# 4_Digital_Isolator.net
KiCad netlist of a schematic drawn in Altium Designer
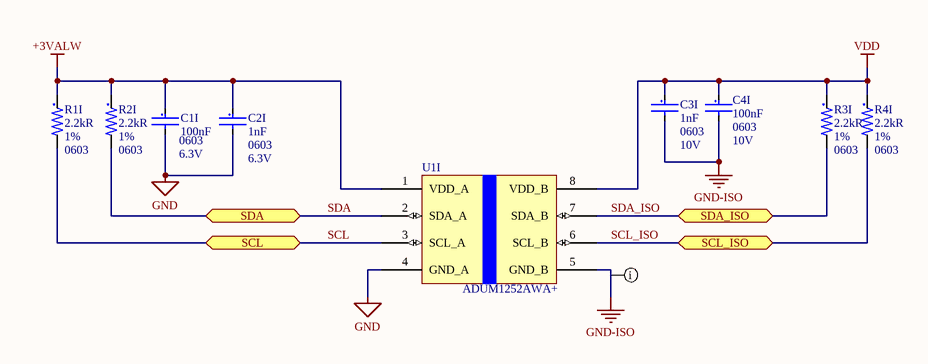
[diagram p0: 4_Digital_Isolator.SchDoc]

(export (version "E")
  (design (tool "Eeschema 10.0.6"))
  (components
    (comp (ref "C1I")
      (value "100nF")
      (footprint "C0603-IPC_C_No_Silk")
      (description "Cap Cer 0.1UF 6.3V X7R 0603")
      (fields
        (field (name "MANUFACTURER") "KYOCERA AVX")
        (field (name "MANUFACTURER PART NUMBER") "KGM15AR70J104KM")
        (field (name "VOLTAGE") "6.3V")
        (field (name "PACKAGE") "0603")
      )
      (libsource (lib "Lib_Capacitor_0603") (part "100nF_6.3V"))
    )
    (comp (ref "C2I")
      (value "1nF")
      (footprint "C0603-IPC_C_No_Silk")
      (description "Cap Ceramic 0.001uF 6.3V C0G 10% SMD 0603 125°C Paper T/R")
      (fields
        (field (name "MANUFACTURER") "Kyocera AVX")
        (field (name "MANUFACTURER PART NUMBER") "06036A102KAT2A")
        (field (name "CASE CODE (IMPERIAL)") "0603")
        (field (name "VOLTAGE RATING") "6.3V")
      )
      (libsource (lib "Lib_Capacitor_0603") (part "1nF_6.3V"))
    )
    (comp (ref "C3I")
      (value "1nF")
      (footprint "C0603-IPC_C_No_Silk")
      (description "Cap Ceramic 0.001uF 10V X7R 10% SMD 0603 125°C Paper T/R")
      (fields
        (field (name "MANUFACTURER") "Yageo")
        (field (name "MANUFACTURER PART NUMBER") "CC0603KRX7R6BB102")
        (field (name "CASE CODE (IMPERIAL)") "0603")
        (field (name "VOLTAGE RATING") "10V")
      )
      (libsource (lib "Lib_Capacitor_0603") (part "1nF_10V"))
    )
    (comp (ref "C4I")
      (value "100nF")
      (footprint "C0603-IPC_C_No_Silk")
      (description "Multilayer Ceramic Capacitor, 0.1 uF, 10 V, ± 10%, X7R, 0603 [1608 Metric]")
      (fields
        (field (name "MANUFACTURER") "KEMET")
        (field (name "MANUFACTURER PART NUMBER") "C0603C104K8RACTU")
        (field (name "VOLTAGE") "10V")
        (field (name "CASE/PACKAGE") "0603")
      )
      (libsource (lib "Lib_Capacitor_0603") (part "100nF_10V"))
    )
    (comp (ref "R1I")
      (value "2.2kR")
      (footprint "R0603-MFG")
      (description "SMD Chip Resistor, 2.2 kOhm, ± 1%, 100 mW, 0603 [1608 Metric], Thick Film, General Purpose")
      (fields
        (field (name "MANUFACTURER") "Yageo")
        (field (name "MANUFACTURER PART NUMBER") "RC0603FR-072K2L")
        (field (name "TOLERANCE") "1%")
        (field (name "CASE/PACKAGE") "0603")
      )
      (libsource (lib "Lib_Register_0603") (part "2.2K"))
    )
    (comp (ref "R2I")
      (value "2.2kR")
      (footprint "R0603-MFG")
      (description "SMD Chip Resistor, 2.2 kOhm, ± 1%, 100 mW, 0603 [1608 Metric], Thick Film, General Purpose")
      (fields
        (field (name "MANUFACTURER") "Yageo")
        (field (name "MANUFACTURER PART NUMBER") "RC0603FR-072K2L")
        (field (name "TOLERANCE") "1%")
        (field (name "CASE/PACKAGE") "0603")
      )
      (libsource (lib "Lib_Register_0603") (part "2.2K"))
    )
    (comp (ref "R3I")
      (value "2.2kR")
      (footprint "R0603-MFG")
      (description "SMD Chip Resistor, 2.2 kOhm, ± 1%, 100 mW, 0603 [1608 Metric], Thick Film, General Purpose")
      (fields
        (field (name "MANUFACTURER") "Yageo")
        (field (name "MANUFACTURER PART NUMBER") "RC0603FR-072K2L")
        (field (name "TOLERANCE") "1%")
        (field (name "CASE/PACKAGE") "0603")
      )
      (libsource (lib "Lib_Register_0603") (part "2.2K"))
    )
    (comp (ref "R4I")
      (value "2.2kR")
      (footprint "R0603-MFG")
      (description "SMD Chip Resistor, 2.2 kOhm, ± 1%, 100 mW, 0603 [1608 Metric], Thick Film, General Purpose")
      (fields
        (field (name "MANUFACTURER") "Yageo")
        (field (name "MANUFACTURER PART NUMBER") "RC0603FR-072K2L")
        (field (name "TOLERANCE") "1%")
        (field (name "CASE/PACKAGE") "0603")
      )
      (libsource (lib "Lib_Register_0603") (part "2.2K"))
    )
    (comp (ref "U1I")
      (value "ADUM1252AWA+")
      (footprint "SOIC-W-8-IPC_A")
      (description "Ultra-Low Power, Bidirectional I2C Isolator with Extended VDD, Idle-Bus Hot-Swap and Low VOL")
      (fields (field (name "MANUFACTURER") "Analog Devices"))
      (libsource (lib "Lib_IC_Voltage_Level_Shift") (part "ADUM1252AWA+"))
    )
  )
  (nets
    (net (code "1") (name "+3VALW") (class "Default")
      (node (ref "C1I") (pin "1") (pinfunction "1_1") (pintype "passive"))
      (node (ref "C2I") (pin "1") (pinfunction "1_1") (pintype "passive"))
      (node (ref "R1I") (pin "1") (pinfunction "1_1") (pintype "passive"))
      (node (ref "R2I") (pin "1") (pinfunction "1_1") (pintype "passive"))
      (node (ref "U1I") (pin "1") (pinfunction "VDD_A_1") (pintype "power_in"))
    )
    (net (code "2") (name "/SCL") (class "Default")
      (node (ref "R1I") (pin "2") (pinfunction "2_2") (pintype "passive"))
      (node (ref "U1I") (pin "3") (pinfunction "SCL_A_3") (pintype "bidirectional"))
    )
    (net (code "3") (name "/SCL_ISO") (class "Default")
      (node (ref "R4I") (pin "2") (pinfunction "2_2") (pintype "passive"))
      (node (ref "U1I") (pin "6") (pinfunction "SCL_B_6") (pintype "bidirectional"))
    )
    (net (code "4") (name "/SDA") (class "Default")
      (node (ref "R2I") (pin "2") (pinfunction "2_2") (pintype "passive"))
      (node (ref "U1I") (pin "2") (pinfunction "SDA_A_2") (pintype "bidirectional"))
    )
    (net (code "5") (name "/SDA_ISO") (class "Default")
      (node (ref "R3I") (pin "2") (pinfunction "2_2") (pintype "passive"))
      (node (ref "U1I") (pin "7") (pinfunction "SDA_B_7") (pintype "bidirectional"))
    )
    (net (code "6") (name "GND") (class "Default")
      (node (ref "C1I") (pin "2") (pinfunction "2_2") (pintype "passive"))
      (node (ref "C2I") (pin "2") (pinfunction "2_2") (pintype "passive"))
      (node (ref "U1I") (pin "4") (pinfunction "GND_A_4") (pintype "power_in"))
    )
    (net (code "7") (name "GND-ISO") (class "Default")
      (node (ref "C3I") (pin "2") (pinfunction "2_2") (pintype "passive"))
      (node (ref "C4I") (pin "2") (pinfunction "2_2") (pintype "passive"))
      (node (ref "U1I") (pin "5") (pinfunction "GND_B_5") (pintype "power_in"))
    )
    (net (code "8") (name "VDD") (class "Default")
      (node (ref "C3I") (pin "1") (pinfunction "1_1") (pintype "passive"))
      (node (ref "C4I") (pin "1") (pinfunction "1_1") (pintype "passive"))
      (node (ref "R3I") (pin "1") (pinfunction "1_1") (pintype "passive"))
      (node (ref "R4I") (pin "1") (pinfunction "1_1") (pintype "passive"))
      (node (ref "U1I") (pin "8") (pinfunction "VDD_B_8") (pintype "power_in"))
    )
  )
)
